# esp32.net
KiCad netlist of a schematic drawn in EAGLE
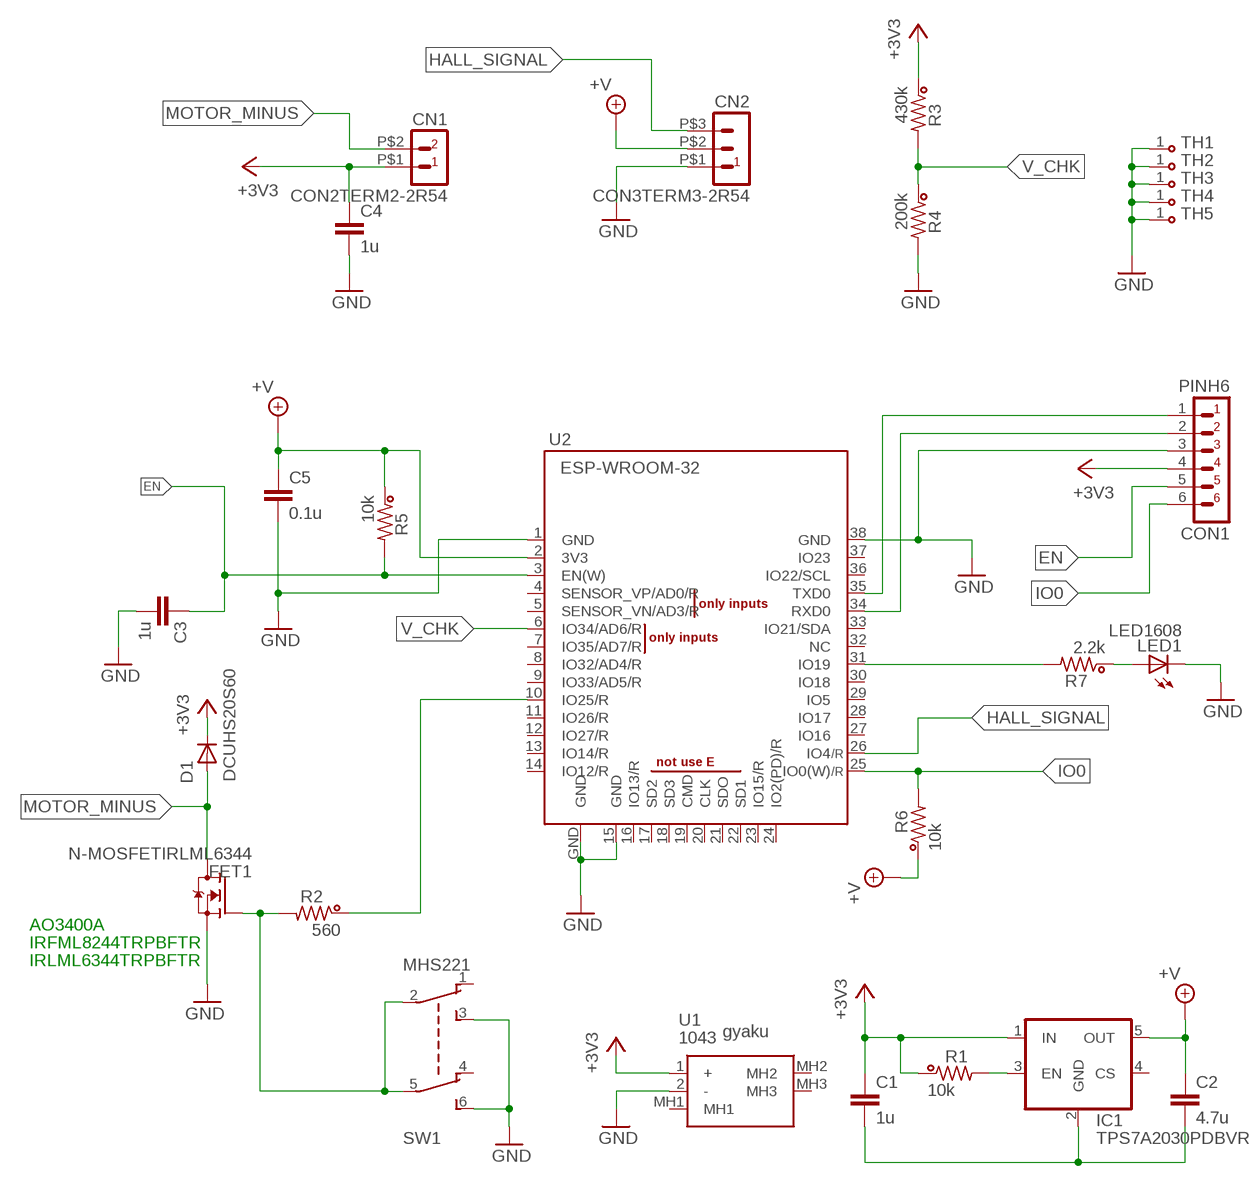
[diagram p0: schematic, sheet 1]

(export (version "E")
  (design (tool "Eeschema 10.0.6"))
  (components
    (comp (ref "C1")
      (value "1u")
      (footprint "eagle-import:2015")
      (libsource (lib "eagle-import") (part "C-CC2015"))
    )
    (comp (ref "C2")
      (value "4.7u")
      (footprint "eagle-import:2015")
      (libsource (lib "eagle-import") (part "C-CC2015"))
    )
    (comp (ref "C3")
      (value "1u")
      (footprint "eagle-import:2015")
      (libsource (lib "eagle-import") (part "C-CC2015"))
    )
    (comp (ref "C4")
      (value "1u")
      (footprint "eagle-import:2015")
      (libsource (lib "eagle-import") (part "C-CC2015"))
    )
    (comp (ref "C5")
      (value "0.1u")
      (footprint "eagle-import:2015")
      (libsource (lib "eagle-import") (part "C-CC2015"))
    )
    (comp (ref "CN1")
      (value "CON2TERM2-2R54")
      (footprint "eagle-import:TERM2-2R54")
      (libsource (lib "eagle-import") (part "CON2TERM2-2R54"))
    )
    (comp (ref "CN2")
      (value "CON3TERM3-2R54")
      (footprint "eagle-import:TERM3-2R54")
      (libsource (lib "eagle-import") (part "CON3TERM3-2R54"))
    )
    (comp (ref "CON1")
      (value "PINH6")
      (footprint "eagle-import:PINH6")
      (libsource (lib "eagle-import") (part "PINH6"))
    )
    (comp (ref "D1")
      (value "DCUHS20S60")
      (footprint "eagle-import:US2H")
      (libsource (lib "eagle-import") (part "DCUHS20S60"))
    )
    (comp (ref "FET1")
      (value "N-MOSFETIRLML6344")
      (footprint "eagle-import:SOT23-3")
      (libsource (lib "eagle-import") (part "N-MOSFETIRLML6344"))
    )
    (comp (ref "IC1")
      (value "TPS7A2030PDBVR")
      (footprint "eagle-import:SOT23-5")
      (libsource (lib "eagle-import") (part "TLV703"))
    )
    (comp (ref "LED1")
      (value "LED1608")
      (footprint "eagle-import:LED1608")
      (libsource (lib "eagle-import") (part "LED1608"))
    )
    (comp (ref "R1")
      (value "10k")
      (footprint "eagle-import:1608")
      (libsource (lib "eagle-import") (part "R-CC1608"))
    )
    (comp (ref "R2")
      (value "560")
      (footprint "eagle-import:1608")
      (libsource (lib "eagle-import") (part "R-CC1608"))
    )
    (comp (ref "R3")
      (value "430k")
      (footprint "eagle-import:1608")
      (libsource (lib "eagle-import") (part "R-CC1608"))
    )
    (comp (ref "R4")
      (value "200k")
      (footprint "eagle-import:1608")
      (libsource (lib "eagle-import") (part "R-CC1608"))
    )
    (comp (ref "R5")
      (value "10k")
      (footprint "eagle-import:1608")
      (libsource (lib "eagle-import") (part "R-CC1608"))
    )
    (comp (ref "R6")
      (value "10k")
      (footprint "eagle-import:1608")
      (libsource (lib "eagle-import") (part "R-CC1608"))
    )
    (comp (ref "R7")
      (value "2.2k")
      (footprint "eagle-import:1608")
      (libsource (lib "eagle-import") (part "R-CC1608"))
    )
    (comp (ref "SW1")
      (value "MHS221")
      (footprint "eagle-import:MHS221")
      (libsource (lib "eagle-import") (part "MHS221"))
    )
    (comp (ref "TH1")
      (value "THTH220")
      (footprint "eagle-import:TH220")
      (libsource (lib "eagle-import") (part "THTH220"))
    )
    (comp (ref "TH2")
      (value "THTH220")
      (footprint "eagle-import:TH220")
      (libsource (lib "eagle-import") (part "THTH220"))
    )
    (comp (ref "TH3")
      (value "THTH220")
      (footprint "eagle-import:TH220")
      (libsource (lib "eagle-import") (part "THTH220"))
    )
    (comp (ref "TH4")
      (value "THTH220")
      (footprint "eagle-import:TH220")
      (libsource (lib "eagle-import") (part "THTH220"))
    )
    (comp (ref "TH5")
      (value "THGG")
      (footprint "eagle-import:TH6-GG")
      (libsource (lib "eagle-import") (part "THGG"))
    )
    (comp (ref "U1")
      (value "1043")
      (footprint "eagle-import:1043")
      (fields (field (name "MOUSER_PART_NUMBER") "534-1043"))
      (libsource (lib "eagle-import") (part "1043"))
    )
    (comp (ref "U2")
      (value "ESP-WROOM-32")
      (footprint "eagle-import:ESP-WROOM-32")
      (libsource (lib "eagle-import") (part "ESP-WROOM-32"))
    )
  )
  (nets
    (net (code "1") (name "+3V3") (class "Default")
      (node (ref "C1") (pin "1") (pinfunction "1_1") (pintype "passive"))
      (node (ref "C4") (pin "1") (pinfunction "1_1") (pintype "passive"))
      (node (ref "CN1") (pin "P$1") (pinfunction "1_P$1") (pintype "passive"))
      (node (ref "CON1") (pin "4") (pinfunction "4_4") (pintype "passive"))
      (node (ref "D1") (pin "C") (pinfunction "C_C") (pintype "passive"))
      (node (ref "IC1") (pin "1") (pinfunction "IN_1") (pintype "input"))
      (node (ref "R1") (pin "1") (pinfunction "1_1") (pintype "passive"))
      (node (ref "R3") (pin "1") (pinfunction "1_1") (pintype "passive"))
      (node (ref "U1") (pin "1") (pinfunction "+_1") (pintype "bidirectional"))
    )
    (net (code "2") (name "+V") (class "Default")
      (node (ref "C2") (pin "1") (pinfunction "1_1") (pintype "passive"))
      (node (ref "C5") (pin "1") (pinfunction "1_1") (pintype "passive"))
      (node (ref "CN2") (pin "P$2") (pinfunction "2_P$2") (pintype "passive"))
      (node (ref "IC1") (pin "5") (pinfunction "OUT_5") (pintype "passive"))
      (node (ref "R5") (pin "1") (pinfunction "1_1") (pintype "passive"))
      (node (ref "R6") (pin "1") (pinfunction "1_1") (pintype "passive"))
      (node (ref "U2") (pin "2") (pinfunction "3V3_2") (pintype "bidirectional"))
    )
    (net (code "3") (name "EN") (class "Default")
      (node (ref "C3") (pin "1") (pinfunction "1_1") (pintype "passive"))
      (node (ref "CON1") (pin "5") (pinfunction "5_5") (pintype "passive"))
      (node (ref "R5") (pin "2") (pinfunction "2_2") (pintype "passive"))
      (node (ref "U2") (pin "3") (pinfunction "EN(W)_3") (pintype "bidirectional"))
    )
    (net (code "4") (name "GND") (class "Default")
      (node (ref "C1") (pin "2") (pinfunction "2_2") (pintype "passive"))
      (node (ref "C2") (pin "2") (pinfunction "2_2") (pintype "passive"))
      (node (ref "C3") (pin "2") (pinfunction "2_2") (pintype "passive"))
      (node (ref "C4") (pin "2") (pinfunction "2_2") (pintype "passive"))
      (node (ref "C5") (pin "2") (pinfunction "2_2") (pintype "passive"))
      (node (ref "CN2") (pin "P$1") (pinfunction "1_P$1") (pintype "passive"))
      (node (ref "CON1") (pin "3") (pinfunction "3_3") (pintype "passive"))
      (node (ref "FET1") (pin "2") (pinfunction "S_2") (pintype "passive"))
      (node (ref "IC1") (pin "2") (pinfunction "GND_2") (pintype "power_in"))
      (node (ref "LED1") (pin "K") (pinfunction "C_K") (pintype "passive"))
      (node (ref "R4") (pin "2") (pinfunction "2_2") (pintype "passive"))
      (node (ref "SW1") (pin "3") (pinfunction "3_3") (pintype "passive"))
      (node (ref "SW1") (pin "6") (pinfunction "6_6") (pintype "passive"))
      (node (ref "TH1") (pin "1") (pinfunction "1_1") (pintype "passive"))
      (node (ref "TH2") (pin "1") (pinfunction "1_1") (pintype "passive"))
      (node (ref "TH3") (pin "1") (pinfunction "1_1") (pintype "passive"))
      (node (ref "TH4") (pin "1") (pinfunction "1_1") (pintype "passive"))
      (node (ref "TH5") (pin "1") (pinfunction "1_1") (pintype "passive"))
      (node (ref "U1") (pin "2") (pinfunction "-_2") (pintype "bidirectional"))
      (node (ref "U2") (pin "1") (pinfunction "GND_1") (pintype "bidirectional"))
      (node (ref "U2") (pin "15") (pinfunction "GND_15") (pintype "bidirectional"))
      (node (ref "U2") (pin "38") (pinfunction "GND_38") (pintype "bidirectional"))
      (node (ref "U2") (pin "GND") (pinfunction "GND_GND") (pintype "bidirectional"))
    )
    (net (code "5") (name "HALL_SIGNAL") (class "Default")
      (node (ref "CN2") (pin "P$3") (pinfunction "3_P$3") (pintype "passive"))
      (node (ref "U2") (pin "26") (pinfunction "IO4_26") (pintype "bidirectional"))
    )
    (net (code "6") (name "IO0") (class "Default")
      (node (ref "CON1") (pin "6") (pinfunction "6_6") (pintype "passive"))
      (node (ref "R6") (pin "2") (pinfunction "2_2") (pintype "passive"))
      (node (ref "U2") (pin "25") (pinfunction "IO0(W)_25") (pintype "bidirectional"))
    )
    (net (code "7") (name "MOTOR_MINUS") (class "Default")
      (node (ref "CN1") (pin "P$2") (pinfunction "2_P$2") (pintype "passive"))
      (node (ref "D1") (pin "A") (pinfunction "A_A") (pintype "passive"))
      (node (ref "FET1") (pin "3") (pinfunction "D_3") (pintype "passive"))
    )
    (net (code "8") (name "Net-(FET1-G)") (class "Default")
      (node (ref "FET1") (pin "1") (pinfunction "G_1") (pintype "passive"))
      (node (ref "R2") (pin "2") (pinfunction "2_2") (pintype "passive"))
      (node (ref "SW1") (pin "2") (pinfunction "2_2") (pintype "passive"))
      (node (ref "SW1") (pin "5") (pinfunction "5_5") (pintype "passive"))
    )
    (net (code "9") (name "Net-(IC1-EN)") (class "Default")
      (node (ref "IC1") (pin "3") (pinfunction "EN_3") (pintype "input"))
      (node (ref "R1") (pin "2") (pinfunction "2_2") (pintype "passive"))
    )
    (net (code "10") (name "Net-(LED1-PadA)") (class "Default")
      (node (ref "LED1") (pin "A") (pinfunction "A_A") (pintype "passive"))
      (node (ref "R7") (pin "1") (pinfunction "1_1") (pintype "passive"))
    )
    (net (code "11") (name "Net-(U2-IO19)") (class "Default")
      (node (ref "R7") (pin "2") (pinfunction "2_2") (pintype "passive"))
      (node (ref "U2") (pin "31") (pinfunction "IO19_31") (pintype "bidirectional"))
    )
    (net (code "12") (name "Net-(U2-IO25{slash}R)") (class "Default")
      (node (ref "R2") (pin "1") (pinfunction "1_1") (pintype "passive"))
      (node (ref "U2") (pin "10") (pinfunction "IO25/R_10") (pintype "bidirectional"))
    )
    (net (code "13") (name "Net-(U2-RXD0)") (class "Default")
      (node (ref "CON1") (pin "2") (pinfunction "2_2") (pintype "passive"))
      (node (ref "U2") (pin "34") (pinfunction "RXD0_34") (pintype "bidirectional"))
    )
    (net (code "14") (name "Net-(U2-TXD0)") (class "Default")
      (node (ref "CON1") (pin "1") (pinfunction "1_1") (pintype "passive"))
      (node (ref "U2") (pin "35") (pinfunction "TXD0_35") (pintype "bidirectional"))
    )
    (net (code "15") (name "V_CHK") (class "Default")
      (node (ref "R3") (pin "2") (pinfunction "2_2") (pintype "passive"))
      (node (ref "R4") (pin "1") (pinfunction "1_1") (pintype "passive"))
      (node (ref "U2") (pin "6") (pinfunction "IO34/AD6/R_6") (pintype "input"))
    )
    (net (code "16") (name "unconnected-(IC1-CS-Pad4)") (class "Default")
      (node (ref "IC1") (pin "4") (pinfunction "CS_4") (pintype "passive"))
    )
    (net (code "17") (name "unconnected-(SW1-Pad1)") (class "Default")
      (node (ref "SW1") (pin "1") (pinfunction "1_1") (pintype "passive"))
    )
    (net (code "18") (name "unconnected-(SW1-Pad4)") (class "Default")
      (node (ref "SW1") (pin "4") (pinfunction "4_4") (pintype "passive"))
    )
    (net (code "19") (name "unconnected-(U1-PadMH1)") (class "Default")
      (node (ref "U1") (pin "MH1") (pinfunction "MH1_MH1") (pintype "bidirectional"))
    )
    (net (code "20") (name "unconnected-(U1-PadMH2)") (class "Default")
      (node (ref "U1") (pin "MH2") (pinfunction "MH2_MH2") (pintype "bidirectional"))
    )
    (net (code "21") (name "unconnected-(U1-PadMH3)") (class "Default")
      (node (ref "U1") (pin "MH3") (pinfunction "MH3_MH3") (pintype "bidirectional"))
    )
    (net (code "22") (name "unconnected-(U2-CLK-Pad20)") (class "Default")
      (node (ref "U2") (pin "20") (pinfunction "CLK_20") (pintype "bidirectional"))
    )
    (net (code "23") (name "unconnected-(U2-CMD-Pad19)") (class "Default")
      (node (ref "U2") (pin "19") (pinfunction "CMD_19") (pintype "bidirectional"))
    )
    (net (code "24") (name "unconnected-(U2-IO2(PD){slash}R-Pad24)") (class "Default")
      (node (ref "U2") (pin "24") (pinfunction "IO2(PD)/R_24") (pintype "bidirectional"))
    )
    (net (code "25") (name "unconnected-(U2-IO5-Pad29)") (class "Default")
      (node (ref "U2") (pin "29") (pinfunction "IO5_29") (pintype "bidirectional"))
    )
    (net (code "26") (name "unconnected-(U2-IO12{slash}R-Pad14)") (class "Default")
      (node (ref "U2") (pin "14") (pinfunction "IO12/R_14") (pintype "bidirectional"))
    )
    (net (code "27") (name "unconnected-(U2-IO13{slash}R-Pad16)") (class "Default")
      (node (ref "U2") (pin "16") (pinfunction "IO13/R_16") (pintype "bidirectional"))
    )
    (net (code "28") (name "unconnected-(U2-IO14{slash}R-Pad13)") (class "Default")
      (node (ref "U2") (pin "13") (pinfunction "IO14/R_13") (pintype "bidirectional"))
    )
    (net (code "29") (name "unconnected-(U2-IO15{slash}R-Pad23)") (class "Default")
      (node (ref "U2") (pin "23") (pinfunction "IO15/R_23") (pintype "bidirectional"))
    )
    (net (code "30") (name "unconnected-(U2-IO16-Pad27)") (class "Default")
      (node (ref "U2") (pin "27") (pinfunction "IO16_27") (pintype "bidirectional"))
    )
    (net (code "31") (name "unconnected-(U2-IO17-Pad28)") (class "Default")
      (node (ref "U2") (pin "28") (pinfunction "IO17_28") (pintype "bidirectional"))
    )
    (net (code "32") (name "unconnected-(U2-IO18-Pad30)") (class "Default")
      (node (ref "U2") (pin "30") (pinfunction "IO18_30") (pintype "bidirectional"))
    )
    (net (code "33") (name "unconnected-(U2-IO21{slash}SDA-Pad33)") (class "Default")
      (node (ref "U2") (pin "33") (pinfunction "IO21/SDA_33") (pintype "bidirectional"))
    )
    (net (code "34") (name "unconnected-(U2-IO22{slash}SCL-Pad36)") (class "Default")
      (node (ref "U2") (pin "36") (pinfunction "IO22/SCL_36") (pintype "bidirectional"))
    )
    (net (code "35") (name "unconnected-(U2-IO23-Pad37)") (class "Default")
      (node (ref "U2") (pin "37") (pinfunction "IO23_37") (pintype "bidirectional"))
    )
    (net (code "36") (name "unconnected-(U2-IO26{slash}R-Pad11)") (class "Default")
      (node (ref "U2") (pin "11") (pinfunction "IO26/R_11") (pintype "bidirectional"))
    )
    (net (code "37") (name "unconnected-(U2-IO27{slash}R-Pad12)") (class "Default")
      (node (ref "U2") (pin "12") (pinfunction "IO27/R_12") (pintype "bidirectional"))
    )
    (net (code "38") (name "unconnected-(U2-IO32{slash}AD4{slash}R-Pad8)") (class "Default")
      (node (ref "U2") (pin "8") (pinfunction "IO32/AD4/R_8") (pintype "bidirectional"))
    )
    (net (code "39") (name "unconnected-(U2-IO33{slash}AD5{slash}R-Pad9)") (class "Default")
      (node (ref "U2") (pin "9") (pinfunction "IO33/AD5/R_9") (pintype "bidirectional"))
    )
    (net (code "40") (name "unconnected-(U2-IO35{slash}AD7{slash}R-Pad7)") (class "Default")
      (node (ref "U2") (pin "7") (pinfunction "IO35/AD7/R_7") (pintype "input"))
    )
    (net (code "41") (name "unconnected-(U2-NC-Pad32)") (class "Default")
      (node (ref "U2") (pin "32") (pinfunction "NC_32") (pintype "bidirectional"))
    )
    (net (code "42") (name "unconnected-(U2-SD1-Pad22)") (class "Default")
      (node (ref "U2") (pin "22") (pinfunction "SD1_22") (pintype "bidirectional"))
    )
    (net (code "43") (name "unconnected-(U2-SD2-Pad17)") (class "Default")
      (node (ref "U2") (pin "17") (pinfunction "SD2_17") (pintype "bidirectional"))
    )
    (net (code "44") (name "unconnected-(U2-SD3-Pad18)") (class "Default")
      (node (ref "U2") (pin "18") (pinfunction "SD3_18") (pintype "bidirectional"))
    )
    (net (code "45") (name "unconnected-(U2-SDO-Pad21)") (class "Default")
      (node (ref "U2") (pin "21") (pinfunction "SDO_21") (pintype "bidirectional"))
    )
    (net (code "46") (name "unconnected-(U2-SENSOR_VN{slash}AD3{slash}R-Pad5)") (class "Default")
      (node (ref "U2") (pin "5") (pinfunction "SENSOR_VN/AD3/R_5") (pintype "input"))
    )
    (net (code "47") (name "unconnected-(U2-SENSOR_VP{slash}AD0{slash}R-Pad4)") (class "Default")
      (node (ref "U2") (pin "4") (pinfunction "SENSOR_VP/AD0/R_4") (pintype "input"))
    )
  )
)
